# Duckietown_Rev_2018A.net
KiCad netlist of a schematic drawn in EAGLE
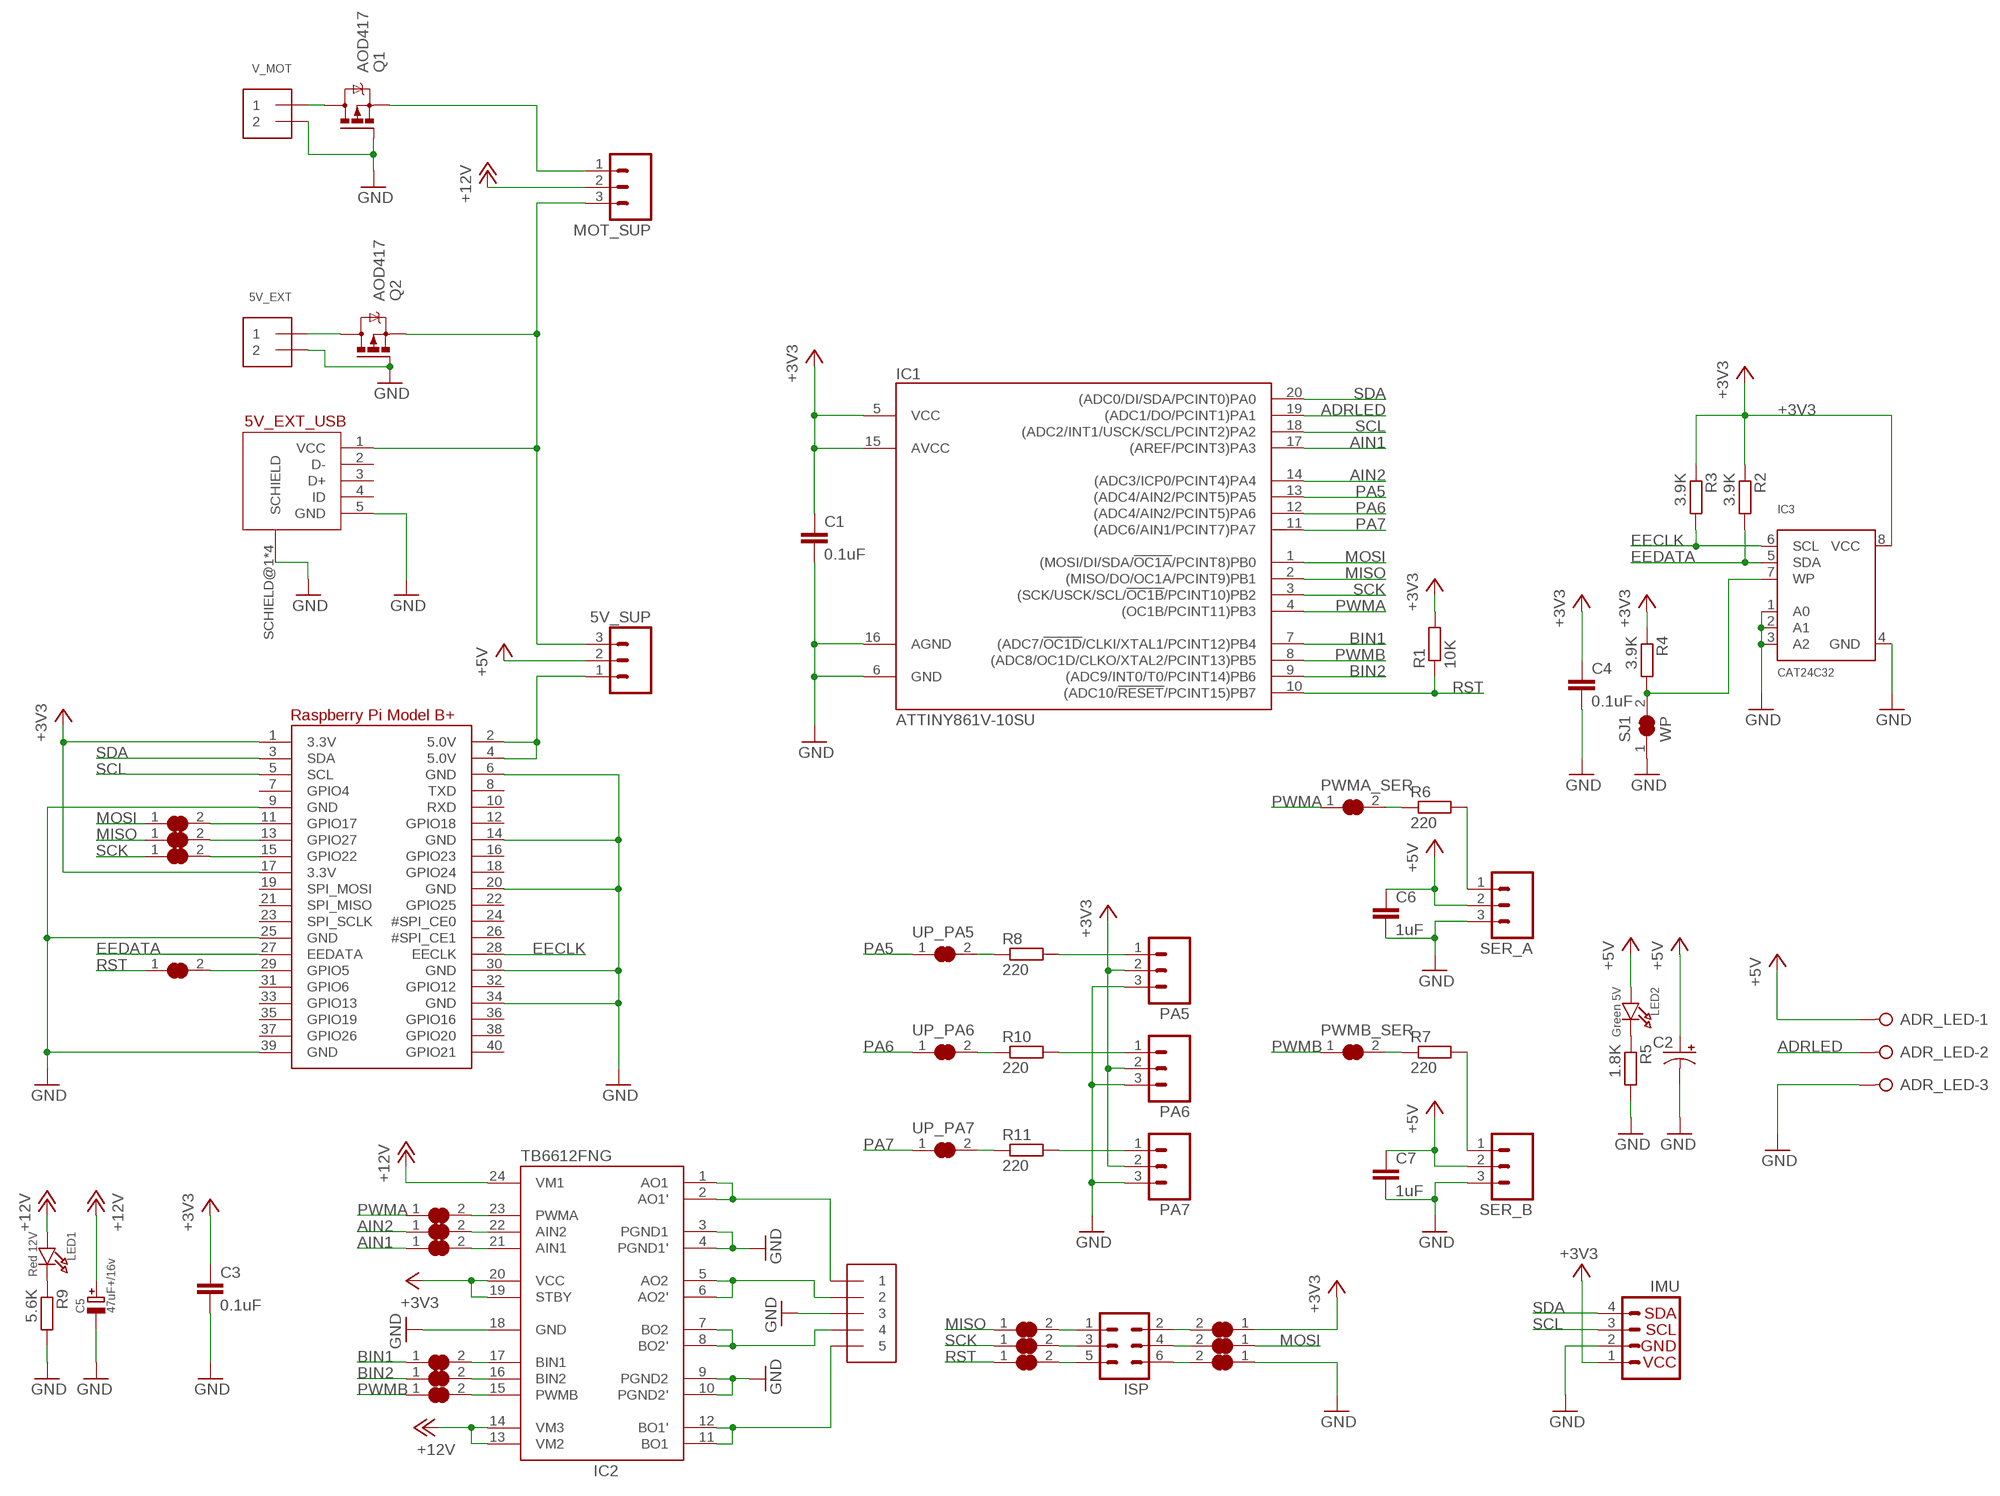
[diagram p0: schematic, sheet 1]

(export (version "E")
  (design (tool "Eeschema 10.0.6"))
  (components
    (comp (ref "5V_EXT")
      (value "TERMBLOCK_1X2")
      (footprint "eagle-import:TERMBLOCK_1X2-3.5MM")
      (libsource (lib "eagle-import") (part "TERMBLOCK_1X2"))
    )
    (comp (ref "5V_EXT_USB")
      (value "MICROUSBCON")
      (footprint "eagle-import:MICROUSBCON")
      (libsource (lib "eagle-import") (part "MICROUSBCON"))
    )
    (comp (ref "5V_SUP")
      (value "M03PTH")
      (footprint "eagle-import:1X03")
      (libsource (lib "eagle-import") (part "M03PTH"))
    )
    (comp (ref "ADR_LED")
      (value "MPT0,5/3-2.54")
      (footprint "eagle-import:MPT0,5_3-2.54")
      (libsource (lib "eagle-import") (part "MPT0,5/3-2.54"))
    )
    (comp (ref "AIN1")
      (value "SOLDERJUMPER_CLOSED")
      (footprint "eagle-import:SOLDERJUMPER_CLOSEDWIRE")
      (libsource (lib "eagle-import") (part "SOLDERJUMPER_CLOSED"))
    )
    (comp (ref "AIN2")
      (value "SOLDERJUMPER_CLOSED")
      (footprint "eagle-import:SOLDERJUMPER_CLOSEDWIRE")
      (libsource (lib "eagle-import") (part "SOLDERJUMPER_CLOSED"))
    )
    (comp (ref "BIN1")
      (value "SOLDERJUMPER_CLOSED")
      (footprint "eagle-import:SOLDERJUMPER_CLOSEDWIRE")
      (libsource (lib "eagle-import") (part "SOLDERJUMPER_CLOSED"))
    )
    (comp (ref "BIN2")
      (value "SOLDERJUMPER_CLOSED")
      (footprint "eagle-import:SOLDERJUMPER_CLOSEDWIRE")
      (libsource (lib "eagle-import") (part "SOLDERJUMPER_CLOSED"))
    )
    (comp (ref "C1")
      (value "0.1uF")
      (footprint "eagle-import:C0603")
      (libsource (lib "eagle-import") (part "C-EUC0603"))
    )
    (comp (ref "C2")
      (value "CPOL-USE3.5-8")
      (footprint "eagle-import:E3,5-8")
      (libsource (lib "eagle-import") (part "CPOL-USE3.5-8"))
    )
    (comp (ref "C3")
      (value "0.1uF")
      (footprint "eagle-import:C0603")
      (libsource (lib "eagle-import") (part "C-EUC0603"))
    )
    (comp (ref "C4")
      (value "0.1uF")
      (footprint "eagle-import:C0603")
      (libsource (lib "eagle-import") (part "C-EUC0603"))
    )
    (comp (ref "C5")
      (value "47uF+/16v")
      (footprint "eagle-import:PANASONIC_C")
      (libsource (lib "eagle-import") (part "CAP_ELECTROLYTICPANASONIC_C"))
    )
    (comp (ref "C6")
      (value "1uF")
      (footprint "eagle-import:C0603")
      (libsource (lib "eagle-import") (part "C-EUC0603"))
    )
    (comp (ref "C7")
      (value "1uF")
      (footprint "eagle-import:C0603")
      (libsource (lib "eagle-import") (part "C-EUC0603"))
    )
    (comp (ref "GND")
      (value "SOLDERJUMPER_CLOSED")
      (footprint "eagle-import:SOLDERJUMPER_CLOSEDWIRE")
      (libsource (lib "eagle-import") (part "SOLDERJUMPER_CLOSED"))
    )
    (comp (ref "IC1")
      (value "ATTINY861V-10SU")
      (footprint "eagle-import:SO20L")
      (libsource (lib "eagle-import") (part "ATTINY861V-10SU"))
    )
    (comp (ref "IC2")
      (value "TB6612FNG")
      (footprint "eagle-import:SSOP24")
      (libsource (lib "eagle-import") (part "TB6612FNG"))
    )
    (comp (ref "IC3")
      (value "CAT24C32")
      (footprint "eagle-import:SOIC8_150MIL")
      (libsource (lib "eagle-import") (part "EEPROM_I2C_SOIC8_GENERIC"))
    )
    (comp (ref "IMU")
      (value "I2C_IMU_L3GD20H+LSM303")
      (footprint "eagle-import:1X04")
      (libsource (lib "eagle-import") (part "I2C_IMU_L3GD20H+LSM303"))
    )
    (comp (ref "ISP")
      (value "ML6")
      (footprint "eagle-import:ML6")
      (libsource (lib "eagle-import") (part "ML6"))
    )
    (comp (ref "LED1")
      (value "Red 12V")
      (footprint "eagle-import:CHIPLED_0805_NOOUTLINE")
      (libsource (lib "eagle-import") (part "LED0805_NOOUTLINE"))
    )
    (comp (ref "LED2")
      (value "Green 5V")
      (footprint "eagle-import:CHIPLED_0805_NOOUTLINE")
      (libsource (lib "eagle-import") (part "LED0805_NOOUTLINE"))
    )
    (comp (ref "MISO")
      (value "SOLDERJUMPER_CLOSED")
      (footprint "eagle-import:SOLDERJUMPER_CLOSEDWIRE")
      (libsource (lib "eagle-import") (part "SOLDERJUMPER_CLOSED"))
    )
    (comp (ref "MOSI")
      (value "SOLDERJUMPER_CLOSED")
      (footprint "eagle-import:SOLDERJUMPER_CLOSEDWIRE")
      (libsource (lib "eagle-import") (part "SOLDERJUMPER_CLOSED"))
    )
    (comp (ref "MOTA")
      (value "1X5")
      (footprint "eagle-import:1X05-3.5MM")
      (libsource (lib "eagle-import") (part "1X5"))
    )
    (comp (ref "MOT_SUP")
      (value "M03PTH")
      (footprint "eagle-import:1X03")
      (libsource (lib "eagle-import") (part "M03PTH"))
    )
    (comp (ref "PA5")
      (value "M03PTH")
      (footprint "eagle-import:1X03")
      (libsource (lib "eagle-import") (part "M03PTH"))
    )
    (comp (ref "PA6")
      (value "M03PTH")
      (footprint "eagle-import:1X03")
      (libsource (lib "eagle-import") (part "M03PTH"))
    )
    (comp (ref "PA7")
      (value "M03PTH")
      (footprint "eagle-import:1X03")
      (libsource (lib "eagle-import") (part "M03PTH"))
    )
    (comp (ref "PWMA")
      (value "SOLDERJUMPER_CLOSED")
      (footprint "eagle-import:SOLDERJUMPER_CLOSEDWIRE")
      (libsource (lib "eagle-import") (part "SOLDERJUMPER_CLOSED"))
    )
    (comp (ref "PWMA_SER")
      (value "SOLDERJUMPER_CLOSED")
      (footprint "eagle-import:SOLDERJUMPER_CLOSEDWIRE")
      (libsource (lib "eagle-import") (part "SOLDERJUMPER_CLOSED"))
    )
    (comp (ref "PWMB")
      (value "SOLDERJUMPER_CLOSED")
      (footprint "eagle-import:SOLDERJUMPER_CLOSEDWIRE")
      (libsource (lib "eagle-import") (part "SOLDERJUMPER_CLOSED"))
    )
    (comp (ref "PWMB_SER")
      (value "SOLDERJUMPER_CLOSED")
      (footprint "eagle-import:SOLDERJUMPER_CLOSEDWIRE")
      (libsource (lib "eagle-import") (part "SOLDERJUMPER_CLOSED"))
    )
    (comp (ref "Q1")
      (value "AOD417")
      (footprint "eagle-import:D-PAK_TO252AA")
      (libsource (lib "eagle-import") (part "IRF?5305R"))
    )
    (comp (ref "Q2")
      (value "AOD417")
      (footprint "eagle-import:D-PAK_TO252AA")
      (libsource (lib "eagle-import") (part "IRF?5305R"))
    )
    (comp (ref "R1")
      (value "10K")
      (footprint "eagle-import:R0603")
      (libsource (lib "eagle-import") (part "R-EU_R0603"))
    )
    (comp (ref "R2")
      (value "3.9K")
      (footprint "eagle-import:R0603")
      (libsource (lib "eagle-import") (part "R-EU_R0603"))
    )
    (comp (ref "R3")
      (value "3.9K")
      (footprint "eagle-import:R0603")
      (libsource (lib "eagle-import") (part "R-EU_R0603"))
    )
    (comp (ref "R4")
      (value "3.9K")
      (footprint "eagle-import:R0603")
      (libsource (lib "eagle-import") (part "R-EU_R0603"))
    )
    (comp (ref "R5")
      (value "1.8K")
      (footprint "eagle-import:R0603")
      (libsource (lib "eagle-import") (part "R-EU_R0603"))
    )
    (comp (ref "R6")
      (value "220")
      (footprint "eagle-import:R0603")
      (libsource (lib "eagle-import") (part "R-EU_R0603"))
    )
    (comp (ref "R7")
      (value "220")
      (footprint "eagle-import:R0603")
      (libsource (lib "eagle-import") (part "R-EU_R0603"))
    )
    (comp (ref "R8")
      (value "220")
      (footprint "eagle-import:R0603")
      (libsource (lib "eagle-import") (part "R-EU_R0603"))
    )
    (comp (ref "R9")
      (value "5.6K")
      (footprint "eagle-import:R0603")
      (libsource (lib "eagle-import") (part "R-EU_R0603"))
    )
    (comp (ref "R10")
      (value "220")
      (footprint "eagle-import:R0603")
      (libsource (lib "eagle-import") (part "R-EU_R0603"))
    )
    (comp (ref "R11")
      (value "220")
      (footprint "eagle-import:R0603")
      (libsource (lib "eagle-import") (part "R-EU_R0603"))
    )
    (comp (ref "RPI2")
      (value "RASPBERRYPI_BPLUS_HATSLOTS")
      (footprint "eagle-import:PI_HAT_SLOTS")
      (libsource (lib "eagle-import") (part "RASPBERRYPI_BPLUS_HATSLOTS"))
    )
    (comp (ref "RP_MISO")
      (value "SOLDERJUMPER_CLOSED")
      (footprint "eagle-import:SOLDERJUMPER_CLOSEDWIRE")
      (libsource (lib "eagle-import") (part "SOLDERJUMPER_CLOSED"))
    )
    (comp (ref "RP_MOSI")
      (value "SOLDERJUMPER_CLOSED")
      (footprint "eagle-import:SOLDERJUMPER_CLOSEDWIRE")
      (libsource (lib "eagle-import") (part "SOLDERJUMPER_CLOSED"))
    )
    (comp (ref "RP_RST")
      (value "SOLDERJUMPER_CLOSED")
      (footprint "eagle-import:SOLDERJUMPER_CLOSEDWIRE")
      (libsource (lib "eagle-import") (part "SOLDERJUMPER_CLOSED"))
    )
    (comp (ref "RP_SCK")
      (value "SOLDERJUMPER_CLOSED")
      (footprint "eagle-import:SOLDERJUMPER_CLOSEDWIRE")
      (libsource (lib "eagle-import") (part "SOLDERJUMPER_CLOSED"))
    )
    (comp (ref "RST")
      (value "SOLDERJUMPER_CLOSED")
      (footprint "eagle-import:SOLDERJUMPER_CLOSEDWIRE")
      (libsource (lib "eagle-import") (part "SOLDERJUMPER_CLOSED"))
    )
    (comp (ref "SCK")
      (value "SOLDERJUMPER_CLOSED")
      (footprint "eagle-import:SOLDERJUMPER_CLOSEDWIRE")
      (libsource (lib "eagle-import") (part "SOLDERJUMPER_CLOSED"))
    )
    (comp (ref "SER_A")
      (value "M03PTH")
      (footprint "eagle-import:1X03")
      (libsource (lib "eagle-import") (part "M03PTH"))
    )
    (comp (ref "SER_B")
      (value "M03PTH")
      (footprint "eagle-import:1X03")
      (libsource (lib "eagle-import") (part "M03PTH"))
    )
    (comp (ref "SJ1")
      (value "WP")
      (footprint "eagle-import:SOLDERJUMPER_CLOSEDWIRE")
      (libsource (lib "eagle-import") (part "SOLDERJUMPER_CLOSED"))
    )
    (comp (ref "UP_PA5")
      (value "SOLDERJUMPER_CLOSED")
      (footprint "eagle-import:SOLDERJUMPER_CLOSEDWIRE")
      (libsource (lib "eagle-import") (part "SOLDERJUMPER_CLOSED"))
    )
    (comp (ref "UP_PA6")
      (value "SOLDERJUMPER_CLOSED")
      (footprint "eagle-import:SOLDERJUMPER_CLOSEDWIRE")
      (libsource (lib "eagle-import") (part "SOLDERJUMPER_CLOSED"))
    )
    (comp (ref "UP_PA7")
      (value "SOLDERJUMPER_CLOSED")
      (footprint "eagle-import:SOLDERJUMPER_CLOSEDWIRE")
      (libsource (lib "eagle-import") (part "SOLDERJUMPER_CLOSED"))
    )
    (comp (ref "VCC")
      (value "SOLDERJUMPER_CLOSED")
      (footprint "eagle-import:SOLDERJUMPER_CLOSEDWIRE")
      (libsource (lib "eagle-import") (part "SOLDERJUMPER_CLOSED"))
    )
    (comp (ref "V_MOT")
      (value "TERMBLOCK_1X2")
      (footprint "eagle-import:TERMBLOCK_1X2-3.5MM")
      (libsource (lib "eagle-import") (part "TERMBLOCK_1X2"))
    )
  )
  (nets
    (net (code "1") (name "+3V3") (class "Default")
      (node (ref "C1") (pin "1") (pinfunction "1_1") (pintype "passive"))
      (node (ref "C3") (pin "1") (pinfunction "1_1") (pintype "passive"))
      (node (ref "C4") (pin "1") (pinfunction "1_1") (pintype "passive"))
      (node (ref "IC1") (pin "15") (pinfunction "AVCC_15") (pintype "power_in"))
      (node (ref "IC1") (pin "5") (pinfunction "VCC_5") (pintype "power_in"))
      (node (ref "IC2") (pin "19") (pinfunction "STBY_19") (pintype "input"))
      (node (ref "IC2") (pin "20") (pinfunction "VCC_20") (pintype "power_in"))
      (node (ref "IC3") (pin "8") (pinfunction "VCC_8") (pintype "power_in"))
      (node (ref "IMU") (pin "1") (pinfunction "1_1") (pintype "passive"))
      (node (ref "PA5") (pin "2") (pinfunction "2_2") (pintype "passive"))
      (node (ref "PA6") (pin "2") (pinfunction "2_2") (pintype "passive"))
      (node (ref "PA7") (pin "2") (pinfunction "2_2") (pintype "passive"))
      (node (ref "R1") (pin "2") (pinfunction "2_2") (pintype "passive"))
      (node (ref "R2") (pin "1") (pinfunction "1_1") (pintype "passive"))
      (node (ref "R3") (pin "1") (pinfunction "1_1") (pintype "passive"))
      (node (ref "R4") (pin "1") (pinfunction "1_1") (pintype "passive"))
      (node (ref "RPI2") (pin "1") (pinfunction "3.3V_1") (pintype "power_in"))
      (node (ref "RPI2") (pin "17") (pinfunction "3.3V_17") (pintype "power_in"))
      (node (ref "VCC") (pin "1") (pinfunction "1_1") (pintype "passive"))
    )
    (net (code "2") (name "+5V") (class "Default")
      (node (ref "5V_SUP") (pin "2") (pinfunction "2_2") (pintype "passive"))
      (node (ref "ADR_LED") (pin "1") (pinfunction "KL_1") (pintype "passive"))
      (node (ref "C2") (pin "+") (pinfunction "+_+") (pintype "passive"))
      (node (ref "C6") (pin "1") (pinfunction "1_1") (pintype "passive"))
      (node (ref "C7") (pin "1") (pinfunction "1_1") (pintype "passive"))
      (node (ref "LED2") (pin "A") (pinfunction "A_A") (pintype "passive"))
      (node (ref "SER_A") (pin "2") (pinfunction "2_2") (pintype "passive"))
      (node (ref "SER_B") (pin "2") (pinfunction "2_2") (pintype "passive"))
    )
    (net (code "3") (name "+12V") (class "Default")
      (node (ref "C5") (pin "+") (pinfunction "+_+") (pintype "passive"))
      (node (ref "IC2") (pin "13") (pinfunction "VM2_13") (pintype "power_in"))
      (node (ref "IC2") (pin "14") (pinfunction "VM3_14") (pintype "power_in"))
      (node (ref "IC2") (pin "24") (pinfunction "VM1_24") (pintype "power_in"))
      (node (ref "LED1") (pin "A") (pinfunction "A_A") (pintype "passive"))
      (node (ref "MOT_SUP") (pin "2") (pinfunction "2_2") (pintype "passive"))
    )
    (net (code "4") (name "/ADRLED") (class "Default")
      (node (ref "ADR_LED") (pin "2") (pinfunction "KL_2") (pintype "passive"))
      (node (ref "IC1") (pin "19") (pinfunction "(ADC1/DO/PCINT1)PA1_19") (pintype "bidirectional"))
    )
    (net (code "5") (name "/AIN1") (class "Default")
      (node (ref "AIN1") (pin "1") (pinfunction "1_1") (pintype "passive"))
      (node (ref "IC1") (pin "17") (pinfunction "(AREF/PCINT3)PA3_17") (pintype "bidirectional"))
    )
    (net (code "6") (name "/AIN2") (class "Default")
      (node (ref "AIN2") (pin "1") (pinfunction "1_1") (pintype "passive"))
      (node (ref "IC1") (pin "14") (pinfunction "(ADC3/ICP0/PCINT4)PA4_14") (pintype "bidirectional"))
    )
    (net (code "7") (name "/BIN1") (class "Default")
      (node (ref "BIN1") (pin "1") (pinfunction "1_1") (pintype "passive"))
      (node (ref "IC1") (pin "7") (pinfunction "(ADC7/~{OC1D}/CLKI/XTAL1/PCINT12)PB4_7") (pintype "bidirectional"))
    )
    (net (code "8") (name "/BIN2") (class "Default")
      (node (ref "BIN2") (pin "1") (pinfunction "1_1") (pintype "passive"))
      (node (ref "IC1") (pin "9") (pinfunction "(ADC9/INT0/T0/PCINT14)PB6_9") (pintype "bidirectional"))
    )
    (net (code "9") (name "/EECLK") (class "Default")
      (node (ref "IC3") (pin "6") (pinfunction "SCL_6") (pintype "input"))
      (node (ref "R3") (pin "2") (pinfunction "2_2") (pintype "passive"))
      (node (ref "RPI2") (pin "28") (pinfunction "EECLK_28") (pintype "power_in"))
    )
    (net (code "10") (name "/EEDATA") (class "Default")
      (node (ref "IC3") (pin "5") (pinfunction "SDA_5") (pintype "bidirectional"))
      (node (ref "R2") (pin "2") (pinfunction "2_2") (pintype "passive"))
      (node (ref "RPI2") (pin "27") (pinfunction "EEDATA_27") (pintype "bidirectional"))
    )
    (net (code "11") (name "/GPIO6") (class "Default")
      (node (ref "RPI2") (pin "31") (pinfunction "GPIO6_31") (pintype "power_in"))
    )
    (net (code "12") (name "/GPIO16") (class "Default")
      (node (ref "RPI2") (pin "36") (pinfunction "GPIO16_36") (pintype "power_in"))
    )
    (net (code "13") (name "/MISO") (class "Default")
      (node (ref "IC1") (pin "2") (pinfunction "(MISO/DO/OC1A/PCINT9)PB1_2") (pintype "bidirectional"))
      (node (ref "MISO") (pin "1") (pinfunction "1_1") (pintype "passive"))
      (node (ref "RP_MISO") (pin "1") (pinfunction "1_1") (pintype "passive"))
    )
    (net (code "14") (name "/MOSI") (class "Default")
      (node (ref "IC1") (pin "1") (pinfunction "(MOSI/DI/SDA/~{OC1A}/PCINT8)PB0_1") (pintype "bidirectional"))
      (node (ref "MOSI") (pin "1") (pinfunction "1_1") (pintype "passive"))
      (node (ref "RP_MOSI") (pin "1") (pinfunction "1_1") (pintype "passive"))
    )
    (net (code "15") (name "/PA5") (class "Default")
      (node (ref "IC1") (pin "13") (pinfunction "(ADC4/AIN2/PCINT5)PA5_13") (pintype "bidirectional"))
      (node (ref "UP_PA5") (pin "1") (pinfunction "1_1") (pintype "passive"))
    )
    (net (code "16") (name "/PA6") (class "Default")
      (node (ref "IC1") (pin "12") (pinfunction "(ADC4/AIN2/PCINT5)PA6_12") (pintype "bidirectional"))
      (node (ref "UP_PA6") (pin "1") (pinfunction "1_1") (pintype "passive"))
    )
    (net (code "17") (name "/PA7") (class "Default")
      (node (ref "IC1") (pin "11") (pinfunction "(ADC6/AIN1/PCINT7)PA7_11") (pintype "bidirectional"))
      (node (ref "UP_PA7") (pin "1") (pinfunction "1_1") (pintype "passive"))
    )
    (net (code "18") (name "/PWMA") (class "Default")
      (node (ref "IC1") (pin "4") (pinfunction "(OC1B/PCINT11)PB3_4") (pintype "bidirectional"))
      (node (ref "PWMA") (pin "1") (pinfunction "1_1") (pintype "passive"))
      (node (ref "PWMA_SER") (pin "1") (pinfunction "1_1") (pintype "passive"))
    )
    (net (code "19") (name "/PWMB") (class "Default")
      (node (ref "IC1") (pin "8") (pinfunction "(ADC8/OC1D/CLKO/XTAL2/PCINT13)PB5_8") (pintype "bidirectional"))
      (node (ref "PWMB") (pin "1") (pinfunction "1_1") (pintype "passive"))
      (node (ref "PWMB_SER") (pin "1") (pinfunction "1_1") (pintype "passive"))
    )
    (net (code "20") (name "/RST") (class "Default")
      (node (ref "IC1") (pin "10") (pinfunction "(ADC10/~{RESET}/PCINT15)PB7_10") (pintype "bidirectional"))
      (node (ref "R1") (pin "1") (pinfunction "1_1") (pintype "passive"))
      (node (ref "RP_RST") (pin "1") (pinfunction "1_1") (pintype "passive"))
      (node (ref "RST") (pin "1") (pinfunction "1_1") (pintype "passive"))
    )
    (net (code "21") (name "/SCK") (class "Default")
      (node (ref "IC1") (pin "3") (pinfunction "(SCK/USCK/SCL/~{OC1B}/PCINT10)PB2_3") (pintype "bidirectional"))
      (node (ref "RP_SCK") (pin "1") (pinfunction "1_1") (pintype "passive"))
      (node (ref "SCK") (pin "1") (pinfunction "1_1") (pintype "passive"))
    )
    (net (code "22") (name "/SCL") (class "Default")
      (node (ref "IC1") (pin "18") (pinfunction "(ADC2/INT1/USCK/SCL/PCINT2)PA2_18") (pintype "bidirectional"))
      (node (ref "IMU") (pin "3") (pinfunction "3_3") (pintype "passive"))
      (node (ref "RPI2") (pin "5") (pinfunction "SCL_5") (pintype "bidirectional"))
    )
    (net (code "23") (name "/SDA") (class "Default")
      (node (ref "IC1") (pin "20") (pinfunction "(ADC0/DI/SDA/PCINT0)PA0_20") (pintype "bidirectional"))
      (node (ref "IMU") (pin "4") (pinfunction "4_4") (pintype "passive"))
      (node (ref "RPI2") (pin "3") (pinfunction "SDA_3") (pintype "bidirectional"))
    )
    (net (code "24") (name "GND") (class "Default")
      (node (ref "5V_EXT") (pin "2") (pinfunction "2_2") (pintype "passive"))
      (node (ref "5V_EXT_USB") (pin "5") (pinfunction "GND_5") (pintype "power_in"))
      (node (ref "5V_EXT_USB") (pin "SCHIELD@1") (pinfunction "SCHIELD_SCHIELD@1") (pintype "bidirectional"))
      (node (ref "5V_EXT_USB") (pin "SCHIELD@2") (pinfunction "SCHIELD_SCHIELD@2") (pintype "bidirectional"))
      (node (ref "5V_EXT_USB") (pin "SCHIELD@3") (pinfunction "SCHIELD_SCHIELD@3") (pintype "bidirectional"))
      (node (ref "5V_EXT_USB") (pin "SCHIELD@4") (pinfunction "SCHIELD_SCHIELD@4") (pintype "bidirectional"))
      (node (ref "ADR_LED") (pin "3") (pinfunction "KL_3") (pintype "passive"))
      (node (ref "C1") (pin "2") (pinfunction "2_2") (pintype "passive"))
      (node (ref "C2") (pin "-") (pinfunction "-_-") (pintype "passive"))
      (node (ref "C3") (pin "2") (pinfunction "2_2") (pintype "passive"))
      (node (ref "C4") (pin "2") (pinfunction "2_2") (pintype "passive"))
      (node (ref "C5") (pin "-") (pinfunction "-_-") (pintype "passive"))
      (node (ref "C6") (pin "2") (pinfunction "2_2") (pintype "passive"))
      (node (ref "C7") (pin "2") (pinfunction "2_2") (pintype "passive"))
      (node (ref "GND") (pin "1") (pinfunction "1_1") (pintype "passive"))
      (node (ref "IC1") (pin "16") (pinfunction "AGND_16") (pintype "power_in"))
      (node (ref "IC1") (pin "6") (pinfunction "GND_6") (pintype "power_in"))
      (node (ref "IC2") (pin "10") (pinfunction "PGND2'_10") (pintype "power_in"))
      (node (ref "IC2") (pin "18") (pinfunction "GND_18") (pintype "power_in"))
      (node (ref "IC2") (pin "3") (pinfunction "PGND1_3") (pintype "power_in"))
      (node (ref "IC2") (pin "4") (pinfunction "PGND1'_4") (pintype "power_in"))
      (node (ref "IC2") (pin "9") (pinfunction "PGND2_9") (pintype "power_in"))
      (node (ref "IC3") (pin "1") (pinfunction "A0_1") (pintype "input"))
      (node (ref "IC3") (pin "2") (pinfunction "A1_2") (pintype "input"))
      (node (ref "IC3") (pin "3") (pinfunction "A2_3") (pintype "input"))
      (node (ref "IC3") (pin "4") (pinfunction "GND_4") (pintype "power_in"))
      (node (ref "IMU") (pin "2") (pinfunction "2_2") (pintype "passive"))
      (node (ref "MOTA") (pin "3") (pinfunction "3_3") (pintype "passive"))
      (node (ref "PA5") (pin "3") (pinfunction "3_3") (pintype "passive"))
      (node (ref "PA6") (pin "3") (pinfunction "3_3") (pintype "passive"))
      (node (ref "PA7") (pin "3") (pinfunction "3_3") (pintype "passive"))
      (node (ref "Q1") (pin "1") (pinfunction "G_1") (pintype "passive"))
      (node (ref "Q2") (pin "1") (pinfunction "G_1") (pintype "passive"))
      (node (ref "R5") (pin "2") (pinfunction "2_2") (pintype "passive"))
      (node (ref "R9") (pin "2") (pinfunction "2_2") (pintype "passive"))
      (node (ref "RPI2") (pin "14") (pinfunction "GND_14") (pintype "power_in"))
      (node (ref "RPI2") (pin "20") (pinfunction "GND_20") (pintype "power_in"))
      (node (ref "RPI2") (pin "25") (pinfunction "GND_25") (pintype "power_in"))
      (node (ref "RPI2") (pin "30") (pinfunction "GND_30") (pintype "bidirectional"))
      (node (ref "RPI2") (pin "34") (pinfunction "GND_34") (pintype "bidirectional"))
      (node (ref "RPI2") (pin "39") (pinfunction "GND_39") (pintype "power_in"))
      (node (ref "RPI2") (pin "6") (pinfunction "GND_6") (pintype "power_in"))
      (node (ref "RPI2") (pin "9") (pinfunction "GND_9") (pintype "power_in"))
      (node (ref "SER_A") (pin "3") (pinfunction "3_3") (pintype "passive"))
      (node (ref "SER_B") (pin "3") (pinfunction "3_3") (pintype "passive"))
      (node (ref "SJ1") (pin "1") (pinfunction "1_1") (pintype "passive"))
      (node (ref "V_MOT") (pin "2") (pinfunction "2_2") (pintype "passive"))
    )
    (net (code "25") (name "Net-(5V_EXT_USB-VCC)") (class "Default")
      (node (ref "5V_EXT_USB") (pin "1") (pinfunction "VCC_1") (pintype "power_in"))
      (node (ref "5V_SUP") (pin "3") (pinfunction "3_3") (pintype "passive"))
      (node (ref "MOT_SUP") (pin "3") (pinfunction "3_3") (pintype "passive"))
      (node (ref "Q2") (pin "3") (pinfunction "S_3") (pintype "passive"))
    )
    (net (code "26") (name "Net-(5V_SUP-Pad1)") (class "Default")
      (node (ref "5V_SUP") (pin "1") (pinfunction "1_1") (pintype "passive"))
      (node (ref "RPI2") (pin "2") (pinfunction "5.0V_2") (pintype "power_in"))
      (node (ref "RPI2") (pin "4") (pinfunction "5.0V_4") (pintype "power_in"))
    )
    (net (code "27") (name "Net-(GND-Pad2)") (class "Default")
      (node (ref "GND") (pin "2") (pinfunction "2_2") (pintype "passive"))
      (node (ref "ISP") (pin "6") (pinfunction "6_6") (pintype "passive"))
    )
    (net (code "28") (name "Net-(IC2-AIN1)") (class "Default")
      (node (ref "AIN1") (pin "2") (pinfunction "2_2") (pintype "passive"))
      (node (ref "IC2") (pin "21") (pinfunction "AIN1_21") (pintype "input"))
    )
    (net (code "29") (name "Net-(IC2-AIN2)") (class "Default")
      (node (ref "AIN2") (pin "2") (pinfunction "2_2") (pintype "passive"))
      (node (ref "IC2") (pin "22") (pinfunction "AIN2_22") (pintype "input"))
    )
    (net (code "30") (name "Net-(IC2-AO1')") (class "Default")
      (node (ref "IC2") (pin "1") (pinfunction "AO1_1") (pintype "output"))
      (node (ref "IC2") (pin "2") (pinfunction "AO1'_2") (pintype "output"))
      (node (ref "MOTA") (pin "1") (pinfunction "1_1") (pintype "passive"))
    )
    (net (code "31") (name "Net-(IC2-AO2')") (class "Default")
      (node (ref "IC2") (pin "5") (pinfunction "AO2_5") (pintype "output"))
      (node (ref "IC2") (pin "6") (pinfunction "AO2'_6") (pintype "output"))
      (node (ref "MOTA") (pin "2") (pinfunction "2_2") (pintype "passive"))
    )
    (net (code "32") (name "Net-(IC2-BIN1)") (class "Default")
      (node (ref "BIN1") (pin "2") (pinfunction "2_2") (pintype "passive"))
      (node (ref "IC2") (pin "17") (pinfunction "BIN1_17") (pintype "input"))
    )
    (net (code "33") (name "Net-(IC2-BIN2)") (class "Default")
      (node (ref "BIN2") (pin "2") (pinfunction "2_2") (pintype "passive"))
      (node (ref "IC2") (pin "16") (pinfunction "BIN2_16") (pintype "input"))
    )
    (net (code "34") (name "Net-(IC2-BO1')") (class "Default")
      (node (ref "IC2") (pin "11") (pinfunction "BO1_11") (pintype "output"))
      (node (ref "IC2") (pin "12") (pinfunction "BO1'_12") (pintype "output"))
      (node (ref "MOTA") (pin "5") (pinfunction "5_5") (pintype "passive"))
    )
    (net (code "35") (name "Net-(IC2-BO2')") (class "Default")
      (node (ref "IC2") (pin "7") (pinfunction "BO2_7") (pintype "output"))
      (node (ref "IC2") (pin "8") (pinfunction "BO2'_8") (pintype "output"))
      (node (ref "MOTA") (pin "4") (pinfunction "4_4") (pintype "passive"))
    )
    (net (code "36") (name "Net-(IC2-PWMA)") (class "Default")
      (node (ref "IC2") (pin "23") (pinfunction "PWMA_23") (pintype "input"))
      (node (ref "PWMA") (pin "2") (pinfunction "2_2") (pintype "passive"))
    )
    (net (code "37") (name "Net-(IC2-PWMB)") (class "Default")
      (node (ref "IC2") (pin "15") (pinfunction "PWMB_15") (pintype "input"))
      (node (ref "PWMB") (pin "2") (pinfunction "2_2") (pintype "passive"))
    )
    (net (code "38") (name "Net-(IC3-WP)") (class "Default")
      (node (ref "IC3") (pin "7") (pinfunction "WP_7") (pintype "input"))
      (node (ref "R4") (pin "2") (pinfunction "2_2") (pintype "passive"))
      (node (ref "SJ1") (pin "2") (pinfunction "2_2") (pintype "passive"))
    )
    (net (code "39") (name "Net-(ISP-Pad1)") (class "Default")
      (node (ref "ISP") (pin "1") (pinfunction "1_1") (pintype "passive"))
      (node (ref "MISO") (pin "2") (pinfunction "2_2") (pintype "passive"))
    )
    (net (code "40") (name "Net-(ISP-Pad2)") (class "Default")
      (node (ref "ISP") (pin "2") (pinfunction "2_2") (pintype "passive"))
      (node (ref "VCC") (pin "2") (pinfunction "2_2") (pintype "passive"))
    )
    (net (code "41") (name "Net-(ISP-Pad3)") (class "Default")
      (node (ref "ISP") (pin "3") (pinfunction "3_3") (pintype "passive"))
      (node (ref "SCK") (pin "2") (pinfunction "2_2") (pintype "passive"))
    )
    (net (code "42") (name "Net-(ISP-Pad4)") (class "Default")
      (node (ref "ISP") (pin "4") (pinfunction "4_4") (pintype "passive"))
      (node (ref "MOSI") (pin "2") (pinfunction "2_2") (pintype "passive"))
    )
    (net (code "43") (name "Net-(ISP-Pad5)") (class "Default")
      (node (ref "ISP") (pin "5") (pinfunction "5_5") (pintype "passive"))
      (node (ref "RST") (pin "2") (pinfunction "2_2") (pintype "passive"))
    )
    (net (code "44") (name "Net-(LED1-PadC)") (class "Default")
      (node (ref "LED1") (pin "C") (pinfunction "C_C") (pintype "passive"))
      (node (ref "R9") (pin "1") (pinfunction "1_1") (pintype "passive"))
    )
    (net (code "45") (name "Net-(LED2-PadC)") (class "Default")
      (node (ref "LED2") (pin "C") (pinfunction "C_C") (pintype "passive"))
      (node (ref "R5") (pin "1") (pinfunction "1_1") (pintype "passive"))
    )
    (net (code "46") (name "Net-(PA5-Pad1)") (class "Default")
      (node (ref "PA5") (pin "1") (pinfunction "1_1") (pintype "passive"))
      (node (ref "R8") (pin "2") (pinfunction "2_2") (pintype "passive"))
    )
    (net (code "47") (name "Net-(PA6-Pad1)") (class "Default")
      (node (ref "PA6") (pin "1") (pinfunction "1_1") (pintype "passive"))
      (node (ref "R10") (pin "2") (pinfunction "2_2") (pintype "passive"))
    )
    (net (code "48") (name "Net-(PA7-Pad1)") (class "Default")
      (node (ref "PA7") (pin "1") (pinfunction "1_1") (pintype "passive"))
      (node (ref "R11") (pin "2") (pinfunction "2_2") (pintype "passive"))
    )
    (net (code "49") (name "Net-(PWMA_SER-Pad2)") (class "Default")
      (node (ref "PWMA_SER") (pin "2") (pinfunction "2_2") (pintype "passive"))
      (node (ref "R6") (pin "1") (pinfunction "1_1") (pintype "passive"))
    )
    (net (code "50") (name "Net-(PWMB_SER-Pad2)") (class "Default")
      (node (ref "PWMB_SER") (pin "2") (pinfunction "2_2") (pintype "passive"))
      (node (ref "R7") (pin "1") (pinfunction "1_1") (pintype "passive"))
    )
    (net (code "51") (name "Net-(Q1-D)") (class "Default")
      (node (ref "Q1") (pin "4") (pinfunction "D_4") (pintype "passive"))
      (node (ref "V_MOT") (pin "1") (pinfunction "1_1") (pintype "passive"))
    )
    (net (code "52") (name "Net-(Q1-S)") (class "Default")
      (node (ref "MOT_SUP") (pin "1") (pinfunction "1_1") (pintype "passive"))
      (node (ref "Q1") (pin "3") (pinfunction "S_3") (pintype "passive"))
    )
    (net (code "53") (name "Net-(Q2-D)") (class "Default")
      (node (ref "5V_EXT") (pin "1") (pinfunction "1_1") (pintype "passive"))
      (node (ref "Q2") (pin "4") (pinfunction "D_4") (pintype "passive"))
    )
    (net (code "54") (name "Net-(R6-Pad2)") (class "Default")
      (node (ref "R6") (pin "2") (pinfunction "2_2") (pintype "passive"))
      (node (ref "SER_A") (pin "1") (pinfunction "1_1") (pintype "passive"))
    )
    (net (code "55") (name "Net-(R7-Pad2)") (class "Default")
      (node (ref "R7") (pin "2") (pinfunction "2_2") (pintype "passive"))
      (node (ref "SER_B") (pin "1") (pinfunction "1_1") (pintype "passive"))
    )
    (net (code "56") (name "Net-(R8-Pad1)") (class "Default")
      (node (ref "R8") (pin "1") (pinfunction "1_1") (pintype "passive"))
      (node (ref "UP_PA5") (pin "2") (pinfunction "2_2") (pintype "passive"))
    )
    (net (code "57") (name "Net-(R10-Pad1)") (class "Default")
      (node (ref "R10") (pin "1") (pinfunction "1_1") (pintype "passive"))
      (node (ref "UP_PA6") (pin "2") (pinfunction "2_2") (pintype "passive"))
    )
    (net (code "58") (name "Net-(R11-Pad1)") (class "Default")
      (node (ref "R11") (pin "1") (pinfunction "1_1") (pintype "passive"))
      (node (ref "UP_PA7") (pin "2") (pinfunction "2_2") (pintype "passive"))
    )
    (net (code "59") (name "Net-(RPI2-GPIO5)") (class "Default")
      (node (ref "RPI2") (pin "29") (pinfunction "GPIO5_29") (pintype "bidirectional"))
      (node (ref "RP_RST") (pin "2") (pinfunction "2_2") (pintype "passive"))
    )
    (net (code "60") (name "Net-(RPI2-GPIO17)") (class "Default")
      (node (ref "RPI2") (pin "11") (pinfunction "GPIO17_11") (pintype "bidirectional"))
      (node (ref "RP_MOSI") (pin "2") (pinfunction "2_2") (pintype "passive"))
    )
    (net (code "61") (name "Net-(RPI2-GPIO22)") (class "Default")
      (node (ref "RPI2") (pin "15") (pinfunction "GPIO22_15") (pintype "bidirectional"))
      (node (ref "RP_SCK") (pin "2") (pinfunction "2_2") (pintype "passive"))
    )
    (net (code "62") (name "Net-(RPI2-GPIO27)") (class "Default")
      (node (ref "RPI2") (pin "13") (pinfunction "GPIO27_13") (pintype "bidirectional"))
      (node (ref "RP_MISO") (pin "2") (pinfunction "2_2") (pintype "passive"))
    )
    (net (code "63") (name "unconnected-(5V_EXT_USB-D+-Pad3)") (class "Default")
      (node (ref "5V_EXT_USB") (pin "3") (pinfunction "D+_3") (pintype "bidirectional"))
    )
    (net (code "64") (name "unconnected-(5V_EXT_USB-D--Pad2)") (class "Default")
      (node (ref "5V_EXT_USB") (pin "2") (pinfunction "D-_2") (pintype "bidirectional"))
    )
    (net (code "65") (name "unconnected-(5V_EXT_USB-ID-Pad4)") (class "Default")
      (node (ref "5V_EXT_USB") (pin "4") (pinfunction "ID_4") (pintype "bidirectional"))
    )
    (net (code "66") (name "unconnected-(RPI2-#SPI_CE0-Pad24)") (class "Default")
      (node (ref "RPI2") (pin "24") (pinfunction "#SPI_CE0_24") (pintype "bidirectional"))
    )
    (net (code "67") (name "unconnected-(RPI2-#SPI_CE1-Pad26)") (class "Default")
      (node (ref "RPI2") (pin "26") (pinfunction "#SPI_CE1_26") (pintype "bidirectional"))
    )
    (net (code "68") (name "unconnected-(RPI2-GPIO4-Pad7)") (class "Default")
      (node (ref "RPI2") (pin "7") (pinfunction "GPIO4_7") (pintype "bidirectional"))
    )
    (net (code "69") (name "unconnected-(RPI2-GPIO12-Pad32)") (class "Default")
      (node (ref "RPI2") (pin "32") (pinfunction "GPIO12_32") (pintype "bidirectional"))
    )
    (net (code "70") (name "unconnected-(RPI2-GPIO13-Pad33)") (class "Default")
      (node (ref "RPI2") (pin "33") (pinfunction "GPIO13_33") (pintype "bidirectional"))
    )
    (net (code "71") (name "unconnected-(RPI2-GPIO18-Pad12)") (class "Default")
      (node (ref "RPI2") (pin "12") (pinfunction "GPIO18_12") (pintype "bidirectional"))
    )
    (net (code "72") (name "unconnected-(RPI2-GPIO19-Pad35)") (class "Default")
      (node (ref "RPI2") (pin "35") (pinfunction "GPIO19_35") (pintype "bidirectional"))
    )
    (net (code "73") (name "unconnected-(RPI2-GPIO20-Pad38)") (class "Default")
      (node (ref "RPI2") (pin "38") (pinfunction "GPIO20_38") (pintype "bidirectional"))
    )
    (net (code "74") (name "unconnected-(RPI2-GPIO21-Pad40)") (class "Default")
      (node (ref "RPI2") (pin "40") (pinfunction "GPIO21_40") (pintype "bidirectional"))
    )
    (net (code "75") (name "unconnected-(RPI2-GPIO23-Pad16)") (class "Default")
      (node (ref "RPI2") (pin "16") (pinfunction "GPIO23_16") (pintype "bidirectional"))
    )
    (net (code "76") (name "unconnected-(RPI2-GPIO24-Pad18)") (class "Default")
      (node (ref "RPI2") (pin "18") (pinfunction "GPIO24_18") (pintype "bidirectional"))
    )
    (net (code "77") (name "unconnected-(RPI2-GPIO25-Pad22)") (class "Default")
      (node (ref "RPI2") (pin "22") (pinfunction "GPIO25_22") (pintype "bidirectional"))
    )
    (net (code "78") (name "unconnected-(RPI2-GPIO26-Pad37)") (class "Default")
      (node (ref "RPI2") (pin "37") (pinfunction "GPIO26_37") (pintype "bidirectional"))
    )
    (net (code "79") (name "unconnected-(RPI2-RXD-Pad10)") (class "Default")
      (node (ref "RPI2") (pin "10") (pinfunction "RXD_10") (pintype "bidirectional"))
    )
    (net (code "80") (name "unconnected-(RPI2-SPI_MISO-Pad21)") (class "Default")
      (node (ref "RPI2") (pin "21") (pinfunction "SPI_MISO_21") (pintype "bidirectional"))
    )
    (net (code "81") (name "unconnected-(RPI2-SPI_MOSI-Pad19)") (class "Default")
      (node (ref "RPI2") (pin "19") (pinfunction "SPI_MOSI_19") (pintype "bidirectional"))
    )
    (net (code "82") (name "unconnected-(RPI2-SPI_SCLK-Pad23)") (class "Default")
      (node (ref "RPI2") (pin "23") (pinfunction "SPI_SCLK_23") (pintype "bidirectional"))
    )
    (net (code "83") (name "unconnected-(RPI2-TXD-Pad8)") (class "Default")
      (node (ref "RPI2") (pin "8") (pinfunction "TXD_8") (pintype "output"))
    )
  )
)
